# E_Piano.net
KiCad netlist of a schematic drawn in EAGLE
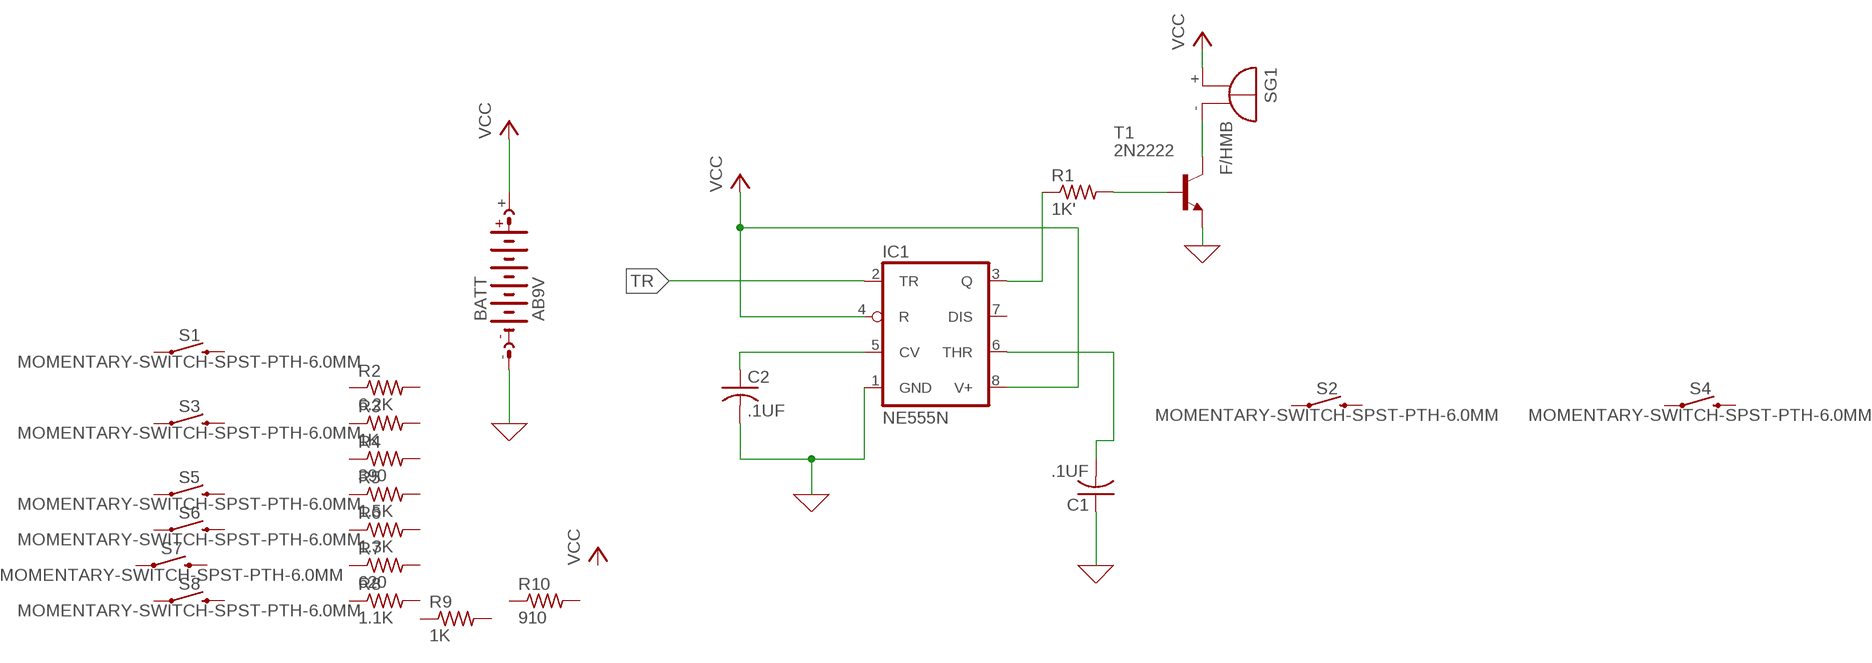
[diagram p0: schematic, sheet 1]

(export (version "E")
  (design (tool "Eeschema 10.0.6"))
  (components
    (comp (ref "BATT")
      (value "AB9V")
      (footprint "eagle-import:AB9V")
      (libsource (lib "eagle-import") (part "AB9V"))
    )
    (comp (ref "C1")
      (value ".1UF")
      (footprint "eagle-import:C025-025X050")
      (libsource (lib "eagle-import") (part "C-US025-025X050"))
    )
    (comp (ref "C2")
      (value ".1UF")
      (footprint "eagle-import:C025-025X050")
      (libsource (lib "eagle-import") (part "C-US025-025X050"))
    )
    (comp (ref "IC1")
      (value "NE555N")
      (footprint "eagle-import:DIL08")
      (libsource (lib "eagle-import") (part "555NNE"))
    )
    (comp (ref "R1")
      (value "1K'")
      (footprint "eagle-import:0309_12")
      (libsource (lib "eagle-import") (part "R-US_0309/12"))
    )
    (comp (ref "R2")
      (value "6.2K")
      (footprint "eagle-import:0309_12")
      (libsource (lib "eagle-import") (part "R-US_0309/12"))
    )
    (comp (ref "R3")
      (value "1K")
      (footprint "eagle-import:0309_12")
      (libsource (lib "eagle-import") (part "R-US_0309/12"))
    )
    (comp (ref "R4")
      (value "390")
      (footprint "eagle-import:0309_12")
      (libsource (lib "eagle-import") (part "R-US_0309/12"))
    )
    (comp (ref "R5")
      (value "1.5K")
      (footprint "eagle-import:0309_12")
      (libsource (lib "eagle-import") (part "R-US_0309/12"))
    )
    (comp (ref "R6")
      (value "1.3K")
      (footprint "eagle-import:0309_12")
      (libsource (lib "eagle-import") (part "R-US_0309/12"))
    )
    (comp (ref "R7")
      (value "620")
      (footprint "eagle-import:0309_12")
      (libsource (lib "eagle-import") (part "R-US_0309/12"))
    )
    (comp (ref "R8")
      (value "1.1K")
      (footprint "eagle-import:0309_12")
      (libsource (lib "eagle-import") (part "R-US_0309/12"))
    )
    (comp (ref "R9")
      (value "1K")
      (footprint "eagle-import:0309_12")
      (libsource (lib "eagle-import") (part "R-US_0309/12"))
    )
    (comp (ref "R10")
      (value "910")
      (footprint "eagle-import:0309_12")
      (libsource (lib "eagle-import") (part "R-US_0309/12"))
    )
    (comp (ref "S1")
      (value "MOMENTARY-SWITCH-SPST-PTH-6.0MM")
      (footprint "eagle-import:TACTILE_SWITCH_PTH_6.0MM")
      (libsource (lib "eagle-import") (part "MOMENTARY-SWITCH-SPST-PTH-6.0MM"))
    )
    (comp (ref "S2")
      (value "MOMENTARY-SWITCH-SPST-PTH-6.0MM")
      (footprint "eagle-import:TACTILE_SWITCH_PTH_6.0MM")
      (libsource (lib "eagle-import") (part "MOMENTARY-SWITCH-SPST-PTH-6.0MM"))
    )
    (comp (ref "S3")
      (value "MOMENTARY-SWITCH-SPST-PTH-6.0MM")
      (footprint "eagle-import:TACTILE_SWITCH_PTH_6.0MM")
      (libsource (lib "eagle-import") (part "MOMENTARY-SWITCH-SPST-PTH-6.0MM"))
    )
    (comp (ref "S4")
      (value "MOMENTARY-SWITCH-SPST-PTH-6.0MM")
      (footprint "eagle-import:TACTILE_SWITCH_PTH_6.0MM")
      (libsource (lib "eagle-import") (part "MOMENTARY-SWITCH-SPST-PTH-6.0MM"))
    )
    (comp (ref "S5")
      (value "MOMENTARY-SWITCH-SPST-PTH-6.0MM")
      (footprint "eagle-import:TACTILE_SWITCH_PTH_6.0MM")
      (libsource (lib "eagle-import") (part "MOMENTARY-SWITCH-SPST-PTH-6.0MM"))
    )
    (comp (ref "S6")
      (value "MOMENTARY-SWITCH-SPST-PTH-6.0MM")
      (footprint "eagle-import:TACTILE_SWITCH_PTH_6.0MM")
      (libsource (lib "eagle-import") (part "MOMENTARY-SWITCH-SPST-PTH-6.0MM"))
    )
    (comp (ref "S7")
      (value "MOMENTARY-SWITCH-SPST-PTH-6.0MM")
      (footprint "eagle-import:TACTILE_SWITCH_PTH_6.0MM")
      (libsource (lib "eagle-import") (part "MOMENTARY-SWITCH-SPST-PTH-6.0MM"))
    )
    (comp (ref "S8")
      (value "MOMENTARY-SWITCH-SPST-PTH-6.0MM")
      (footprint "eagle-import:TACTILE_SWITCH_PTH_6.0MM")
      (libsource (lib "eagle-import") (part "MOMENTARY-SWITCH-SPST-PTH-6.0MM"))
    )
    (comp (ref "SG1")
      (value "F/HMB")
      (footprint "eagle-import:F_HMB")
      (libsource (lib "eagle-import") (part "F/HMB"))
    )
    (comp (ref "T1")
      (value "2N2222")
      (footprint "eagle-import:TO18")
      (libsource (lib "eagle-import") (part "2N2222"))
    )
  )
  (nets
    (net (code "1") (name "GND") (class "Default")
      (node (ref "BATT") (pin "-") (pinfunction "-_-") (pintype "passive"))
      (node (ref "C1") (pin "1") (pinfunction "1_1") (pintype "passive"))
      (node (ref "C2") (pin "2") (pinfunction "2_2") (pintype "passive"))
      (node (ref "IC1") (pin "1") (pinfunction "GND_1") (pintype "power_in"))
      (node (ref "T1") (pin "1") (pinfunction "E_1") (pintype "passive"))
    )
    (net (code "2") (name "Net-(IC1-CV)") (class "Default")
      (node (ref "C2") (pin "1") (pinfunction "1_1") (pintype "passive"))
      (node (ref "IC1") (pin "5") (pinfunction "CV_5") (pintype "input"))
    )
    (net (code "3") (name "Net-(IC1-Q)") (class "Default")
      (node (ref "IC1") (pin "3") (pinfunction "Q_3") (pintype "output"))
      (node (ref "R1") (pin "1") (pinfunction "1_1") (pintype "passive"))
    )
    (net (code "4") (name "Net-(IC1-THR)") (class "Default")
      (node (ref "C1") (pin "2") (pinfunction "2_2") (pintype "passive"))
      (node (ref "IC1") (pin "6") (pinfunction "THR_6") (pintype "input"))
    )
    (net (code "5") (name "Net-(T1-B)") (class "Default")
      (node (ref "R1") (pin "2") (pinfunction "2_2") (pintype "passive"))
      (node (ref "T1") (pin "2") (pinfunction "B_2") (pintype "passive"))
    )
    (net (code "6") (name "Net-(T1-C)") (class "Default")
      (node (ref "SG1") (pin "-") (pinfunction "-_-") (pintype "passive"))
      (node (ref "T1") (pin "3") (pinfunction "C_3") (pintype "passive"))
    )
    (net (code "7") (name "TR") (class "Default")
      (node (ref "IC1") (pin "2") (pinfunction "TR_2") (pintype "input"))
    )
    (net (code "8") (name "VCC") (class "Default")
      (node (ref "BATT") (pin "+") (pinfunction "+_+") (pintype "passive"))
      (node (ref "IC1") (pin "4") (pinfunction "R_4") (pintype "input"))
      (node (ref "IC1") (pin "8") (pinfunction "V+_8") (pintype "power_in"))
      (node (ref "SG1") (pin "+") (pinfunction "+_+") (pintype "passive"))
    )
    (net (code "9") (name "unconnected-(IC1-DIS-Pad7)") (class "Default")
      (node (ref "IC1") (pin "7") (pinfunction "DIS_7") (pintype "input"))
    )
    (net (code "10") (name "unconnected-(R2-Pad1)") (class "Default")
      (node (ref "R2") (pin "1") (pinfunction "1_1") (pintype "passive"))
    )
    (net (code "11") (name "unconnected-(R2-Pad2)") (class "Default")
      (node (ref "R2") (pin "2") (pinfunction "2_2") (pintype "passive"))
    )
    (net (code "12") (name "unconnected-(R3-Pad1)") (class "Default")
      (node (ref "R3") (pin "1") (pinfunction "1_1") (pintype "passive"))
    )
    (net (code "13") (name "unconnected-(R3-Pad2)") (class "Default")
      (node (ref "R3") (pin "2") (pinfunction "2_2") (pintype "passive"))
    )
    (net (code "14") (name "unconnected-(R4-Pad1)") (class "Default")
      (node (ref "R4") (pin "1") (pinfunction "1_1") (pintype "passive"))
    )
    (net (code "15") (name "unconnected-(R4-Pad2)") (class "Default")
      (node (ref "R4") (pin "2") (pinfunction "2_2") (pintype "passive"))
    )
    (net (code "16") (name "unconnected-(R5-Pad1)") (class "Default")
      (node (ref "R5") (pin "1") (pinfunction "1_1") (pintype "passive"))
    )
    (net (code "17") (name "unconnected-(R5-Pad2)") (class "Default")
      (node (ref "R5") (pin "2") (pinfunction "2_2") (pintype "passive"))
    )
    (net (code "18") (name "unconnected-(R6-Pad1)") (class "Default")
      (node (ref "R6") (pin "1") (pinfunction "1_1") (pintype "passive"))
    )
    (net (code "19") (name "unconnected-(R6-Pad2)") (class "Default")
      (node (ref "R6") (pin "2") (pinfunction "2_2") (pintype "passive"))
    )
    (net (code "20") (name "unconnected-(R7-Pad1)") (class "Default")
      (node (ref "R7") (pin "1") (pinfunction "1_1") (pintype "passive"))
    )
    (net (code "21") (name "unconnected-(R7-Pad2)") (class "Default")
      (node (ref "R7") (pin "2") (pinfunction "2_2") (pintype "passive"))
    )
    (net (code "22") (name "unconnected-(R8-Pad1)") (class "Default")
      (node (ref "R8") (pin "1") (pinfunction "1_1") (pintype "passive"))
    )
    (net (code "23") (name "unconnected-(R8-Pad2)") (class "Default")
      (node (ref "R8") (pin "2") (pinfunction "2_2") (pintype "passive"))
    )
    (net (code "24") (name "unconnected-(R9-Pad1)") (class "Default")
      (node (ref "R9") (pin "1") (pinfunction "1_1") (pintype "passive"))
    )
    (net (code "25") (name "unconnected-(R9-Pad2)") (class "Default")
      (node (ref "R9") (pin "2") (pinfunction "2_2") (pintype "passive"))
    )
    (net (code "26") (name "unconnected-(R10-Pad1)") (class "Default")
      (node (ref "R10") (pin "1") (pinfunction "1_1") (pintype "passive"))
    )
    (net (code "27") (name "unconnected-(R10-Pad2)") (class "Default")
      (node (ref "R10") (pin "2") (pinfunction "2_2") (pintype "passive"))
    )
    (net (code "28") (name "unconnected-(S1-2-Pad3)") (class "Default")
      (node (ref "S1") (pin "3") (pinfunction "2_3") (pintype "passive"))
    )
    (net (code "29") (name "unconnected-(S1-Pad1)") (class "Default")
      (node (ref "S1") (pin "1") (pinfunction "1_1") (pintype "passive"))
    )
    (net (code "30") (name "unconnected-(S2-2-Pad3)") (class "Default")
      (node (ref "S2") (pin "3") (pinfunction "2_3") (pintype "passive"))
    )
    (net (code "31") (name "unconnected-(S2-Pad1)") (class "Default")
      (node (ref "S2") (pin "1") (pinfunction "1_1") (pintype "passive"))
    )
    (net (code "32") (name "unconnected-(S3-2-Pad3)") (class "Default")
      (node (ref "S3") (pin "3") (pinfunction "2_3") (pintype "passive"))
    )
    (net (code "33") (name "unconnected-(S3-Pad1)") (class "Default")
      (node (ref "S3") (pin "1") (pinfunction "1_1") (pintype "passive"))
    )
    (net (code "34") (name "unconnected-(S4-2-Pad3)") (class "Default")
      (node (ref "S4") (pin "3") (pinfunction "2_3") (pintype "passive"))
    )
    (net (code "35") (name "unconnected-(S4-Pad1)") (class "Default")
      (node (ref "S4") (pin "1") (pinfunction "1_1") (pintype "passive"))
    )
    (net (code "36") (name "unconnected-(S5-2-Pad3)") (class "Default")
      (node (ref "S5") (pin "3") (pinfunction "2_3") (pintype "passive"))
    )
    (net (code "37") (name "unconnected-(S5-Pad1)") (class "Default")
      (node (ref "S5") (pin "1") (pinfunction "1_1") (pintype "passive"))
    )
    (net (code "38") (name "unconnected-(S6-2-Pad3)") (class "Default")
      (node (ref "S6") (pin "3") (pinfunction "2_3") (pintype "passive"))
    )
    (net (code "39") (name "unconnected-(S6-Pad1)") (class "Default")
      (node (ref "S6") (pin "1") (pinfunction "1_1") (pintype "passive"))
    )
    (net (code "40") (name "unconnected-(S7-2-Pad3)") (class "Default")
      (node (ref "S7") (pin "3") (pinfunction "2_3") (pintype "passive"))
    )
    (net (code "41") (name "unconnected-(S7-Pad1)") (class "Default")
      (node (ref "S7") (pin "1") (pinfunction "1_1") (pintype "passive"))
    )
    (net (code "42") (name "unconnected-(S8-2-Pad3)") (class "Default")
      (node (ref "S8") (pin "3") (pinfunction "2_3") (pintype "passive"))
    )
    (net (code "43") (name "unconnected-(S8-Pad1)") (class "Default")
      (node (ref "S8") (pin "1") (pinfunction "1_1") (pintype "passive"))
    )
  )
)
